# PERIPHERALS.net
KiCad netlist of a schematic drawn in Altium Designer
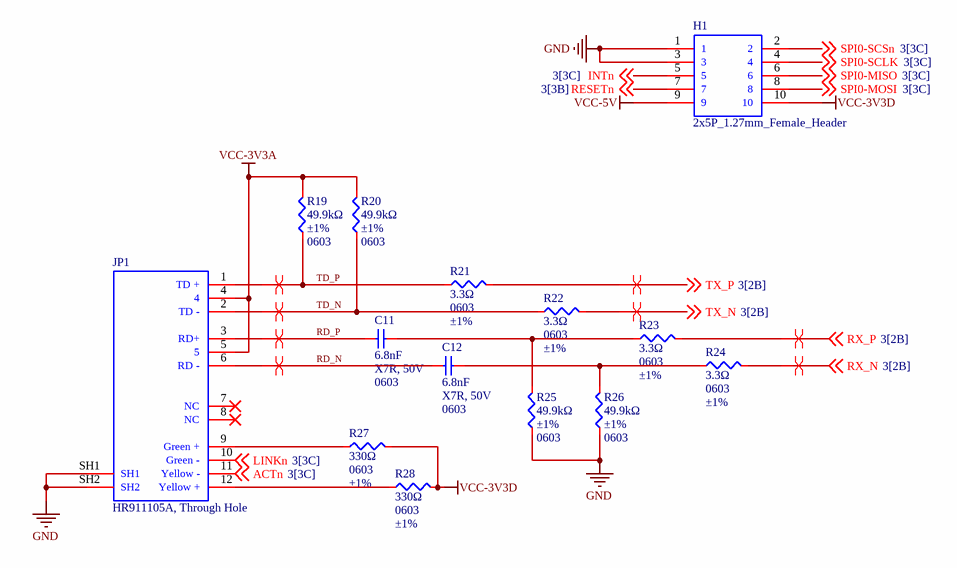
[diagram p0: PERIPHERALS.SchDoc]

(export (version "E")
  (design (tool "Eeschema 10.0.6"))
  (components
    (comp (ref "C11")
      (value "6.8nF")
      (footprint "C0603")
      (description "6.8nF ±10% 50V Ceramic Capacitor X7R 0603")
      (fields
        (field (name "MANUFACTURER") "YAGEO")
        (field (name "MFR. PART") "CC0603KRX7R9BB682")
        (field (name "TEMPERATURE COEFFICIENT") "X7R, 50V")
        (field (name "PACKAGE") "0603")
      )
      (libsource (lib "Capacitor") (part "C0603_MLCC_6.8nF_X7R_50V"))
    )
    (comp (ref "C12")
      (value "6.8nF")
      (footprint "C0603")
      (description "6.8nF ±10% 50V Ceramic Capacitor X7R 0603")
      (fields
        (field (name "MANUFACTURER") "YAGEO")
        (field (name "MFR. PART") "CC0603KRX7R9BB682")
        (field (name "TEMPERATURE COEFFICIENT") "X7R, 50V")
        (field (name "PACKAGE") "0603")
      )
      (libsource (lib "Capacitor") (part "C0603_MLCC_6.8nF_X7R_50V"))
    )
    (comp (ref "H1")
      (value "2x5P_1.27mm_Female_Header")
      (footprint "2x5P, 1.27mm, Female Header")
      (description "Female Header 10 Position 1.27mm Pitch Dual Row Through Hole -40℃~+105℃")
      (fields (field (name "MANUFACTURER") "Megastar") (field (name "MFR. PART") "ZX-PM1.27-2-5PU"))
      (libsource (lib "HEADER") (part "2x5P_1.27mm_Female_Header"))
    )
    (comp (ref "JP1")
      (value "HR911105A, Through Hole")
      (footprint "HR911105A")
      (description "CONN MOD JACK RJ45 TH")
      (fields
        (field (name "MANUFACTURER") "HANRUN(Zhongshan HanRun Elec)")
        (field (name "MFR. PART") "HR911105A")
      )
      (libsource (lib "CONNECTER") (part "HR911105A"))
    )
    (comp (ref "R19")
      (value "49.9kΩ")
      (footprint "R0603")
      (description "100mW Thick Film Resistor 75V ±100ppm/℃ ±1% 49.9kΩ 0603 Chip Resistor - Surface Mount ROHS")
      (fields
        (field (name "MANUFACTURER") "YAGEO")
        (field (name "MFR. PART") "RC0603FR-0749K9L")
        (field (name "TOLERANCE") "±1%")
        (field (name "PACKAGE") "0603")
      )
      (libsource (lib "Resistor") (part "R0603_49.9KΩ_±1%"))
    )
    (comp (ref "R20")
      (value "49.9kΩ")
      (footprint "R0603")
      (description "100mW Thick Film Resistor 75V ±100ppm/℃ ±1% 49.9kΩ 0603 Chip Resistor - Surface Mount ROHS")
      (fields
        (field (name "MANUFACTURER") "YAGEO")
        (field (name "MFR. PART") "RC0603FR-0749K9L")
        (field (name "TOLERANCE") "±1%")
        (field (name "PACKAGE") "0603")
      )
      (libsource (lib "Resistor") (part "R0603_49.9KΩ_±1%"))
    )
    (comp (ref "R21")
      (value "3.3Ω")
      (footprint "R0603")
      (description "3.3Ω ±1% 100mW 0603 Thick Film Resistor")
      (fields
        (field (name "MANUFACTURER") "UNI-ROYAL")
        (field (name "MFR. PART") "0603WAF330KT5E")
        (field (name "PACKAGE") "0603")
        (field (name "TOLERANCE") "±1%")
      )
      (libsource (lib "Resistor") (part "R0603_3.3Ω_±1%"))
    )
    (comp (ref "R22")
      (value "3.3Ω")
      (footprint "R0603")
      (description "3.3Ω ±1% 100mW 0603 Thick Film Resistor")
      (fields
        (field (name "MANUFACTURER") "UNI-ROYAL")
        (field (name "MFR. PART") "0603WAF330KT5E")
        (field (name "PACKAGE") "0603")
        (field (name "TOLERANCE") "±1%")
      )
      (libsource (lib "Resistor") (part "R0603_3.3Ω_±1%"))
    )
    (comp (ref "R23")
      (value "3.3Ω")
      (footprint "R0603")
      (description "3.3Ω ±1% 100mW 0603 Thick Film Resistor")
      (fields
        (field (name "MANUFACTURER") "UNI-ROYAL")
        (field (name "MFR. PART") "0603WAF330KT5E")
        (field (name "PACKAGE") "0603")
        (field (name "TOLERANCE") "±1%")
      )
      (libsource (lib "Resistor") (part "R0603_3.3Ω_±1%"))
    )
    (comp (ref "R24")
      (value "3.3Ω")
      (footprint "R0603")
      (description "3.3Ω ±1% 100mW 0603 Thick Film Resistor")
      (fields
        (field (name "MANUFACTURER") "UNI-ROYAL")
        (field (name "MFR. PART") "0603WAF330KT5E")
        (field (name "PACKAGE") "0603")
        (field (name "TOLERANCE") "±1%")
      )
      (libsource (lib "Resistor") (part "R0603_3.3Ω_±1%"))
    )
    (comp (ref "R25")
      (value "49.9kΩ")
      (footprint "R0603")
      (description "100mW Thick Film Resistor 75V ±100ppm/℃ ±1% 49.9kΩ 0603 Chip Resistor - Surface Mount ROHS")
      (fields
        (field (name "MANUFACTURER") "YAGEO")
        (field (name "MFR. PART") "RC0603FR-0749K9L")
        (field (name "TOLERANCE") "±1%")
        (field (name "PACKAGE") "0603")
      )
      (libsource (lib "Resistor") (part "R0603_49.9KΩ_±1%"))
    )
    (comp (ref "R26")
      (value "49.9kΩ")
      (footprint "R0603")
      (description "100mW Thick Film Resistor 75V ±100ppm/℃ ±1% 49.9kΩ 0603 Chip Resistor - Surface Mount ROHS")
      (fields
        (field (name "MANUFACTURER") "YAGEO")
        (field (name "MFR. PART") "RC0603FR-0749K9L")
        (field (name "TOLERANCE") "±1%")
        (field (name "PACKAGE") "0603")
      )
      (libsource (lib "Resistor") (part "R0603_49.9KΩ_±1%"))
    )
    (comp (ref "R27")
      (value "330Ω")
      (footprint "R0603")
      (description "100mW Thick Film Resistor 75V ±100ppm/℃ ±1% 330Ω 0603 Chip Resistor - Surface Mount ROHS")
      (fields
        (field (name "MANUFACTURER") "YAGEO")
        (field (name "MFR. PART") "RC0603FR-07330RL")
        (field (name "PACKAGE") "0603")
        (field (name "TOLERANCE") "±1%")
      )
      (libsource (lib "Resistor") (part "R0603_330Ω_±1%"))
    )
    (comp (ref "R28")
      (value "330Ω")
      (footprint "R0603")
      (description "100mW Thick Film Resistor 75V ±100ppm/℃ ±1% 330Ω 0603 Chip Resistor - Surface Mount ROHS")
      (fields
        (field (name "MANUFACTURER") "YAGEO")
        (field (name "MFR. PART") "RC0603FR-07330RL")
        (field (name "PACKAGE") "0603")
        (field (name "TOLERANCE") "±1%")
      )
      (libsource (lib "Resistor") (part "R0603_330Ω_±1%"))
    )
  )
  (nets
    (net (code "1") (name "/RD_N") (class "Default")
      (node (ref "C12") (pin "1") (pinfunction "1_1") (pintype "passive"))
      (node (ref "JP1") (pin "6") (pinfunction "RD_-_6") (pintype "passive"))
    )
    (net (code "2") (name "/RD_P") (class "Default")
      (node (ref "C11") (pin "1") (pinfunction "1_1") (pintype "passive"))
      (node (ref "JP1") (pin "3") (pinfunction "RD+_3") (pintype "passive"))
    )
    (net (code "3") (name "/TD_N") (class "Default")
      (node (ref "JP1") (pin "2") (pinfunction "TD_-_2") (pintype "passive"))
      (node (ref "R20") (pin "1") (pinfunction "1_1") (pintype "passive"))
      (node (ref "R22") (pin "1") (pinfunction "1_1") (pintype "passive"))
    )
    (net (code "4") (name "/TD_P") (class "Default")
      (node (ref "JP1") (pin "1") (pinfunction "TD_+_1") (pintype "passive"))
      (node (ref "R19") (pin "1") (pinfunction "1_1") (pintype "passive"))
      (node (ref "R21") (pin "1") (pinfunction "1_1") (pintype "passive"))
    )
    (net (code "5") (name "ACTn") (class "Default")
      (node (ref "JP1") (pin "11") (pinfunction "Yellow_-_11") (pintype "passive"))
    )
    (net (code "6") (name "GND") (class "Default")
      (node (ref "H1") (pin "1") (pinfunction "1_1") (pintype "passive"))
      (node (ref "H1") (pin "3") (pinfunction "3_3") (pintype "passive"))
      (node (ref "JP1") (pin "SH1") (pinfunction "SH1_SH1") (pintype "passive"))
      (node (ref "JP1") (pin "SH2") (pinfunction "SH2_SH2") (pintype "passive"))
      (node (ref "R25") (pin "1") (pinfunction "1_1") (pintype "passive"))
      (node (ref "R26") (pin "1") (pinfunction "1_1") (pintype "passive"))
    )
    (net (code "7") (name "INTn") (class "Default")
      (node (ref "H1") (pin "5") (pinfunction "5_5") (pintype "passive"))
    )
    (net (code "8") (name "LINKn") (class "Default")
      (node (ref "JP1") (pin "10") (pinfunction "Green_-_10") (pintype "passive"))
    )
    (net (code "9") (name "Net-(C11-Pad2)") (class "Default")
      (node (ref "C11") (pin "2") (pinfunction "2_2") (pintype "passive"))
      (node (ref "R23") (pin "1") (pinfunction "1_1") (pintype "passive"))
      (node (ref "R25") (pin "2") (pinfunction "2_2") (pintype "passive"))
    )
    (net (code "10") (name "Net-(C12-Pad2)") (class "Default")
      (node (ref "C12") (pin "2") (pinfunction "2_2") (pintype "passive"))
      (node (ref "R24") (pin "1") (pinfunction "1_1") (pintype "passive"))
      (node (ref "R26") (pin "2") (pinfunction "2_2") (pintype "passive"))
    )
    (net (code "11") (name "Net-(JP1-Green_+)") (class "Default")
      (node (ref "JP1") (pin "9") (pinfunction "Green_+_9") (pintype "passive"))
      (node (ref "R27") (pin "1") (pinfunction "1_1") (pintype "passive"))
    )
    (net (code "12") (name "Net-(JP1-Yellow_+)") (class "Default")
      (node (ref "JP1") (pin "12") (pinfunction "Yellow_+_12") (pintype "passive"))
      (node (ref "R28") (pin "1") (pinfunction "1_1") (pintype "passive"))
    )
    (net (code "13") (name "RESETn") (class "Default")
      (node (ref "H1") (pin "7") (pinfunction "7_7") (pintype "passive"))
    )
    (net (code "14") (name "RX_N") (class "Default")
      (node (ref "R24") (pin "2") (pinfunction "2_2") (pintype "passive"))
    )
    (net (code "15") (name "RX_P") (class "Default")
      (node (ref "R23") (pin "2") (pinfunction "2_2") (pintype "passive"))
    )
    (net (code "16") (name "SPI0-MISO") (class "Default")
      (node (ref "H1") (pin "6") (pinfunction "6_6") (pintype "passive"))
    )
    (net (code "17") (name "SPI0-MOSI") (class "Default")
      (node (ref "H1") (pin "8") (pinfunction "8_8") (pintype "passive"))
    )
    (net (code "18") (name "SPI0-SCLK") (class "Default")
      (node (ref "H1") (pin "4") (pinfunction "4_4") (pintype "passive"))
    )
    (net (code "19") (name "SPI0-SCSn") (class "Default")
      (node (ref "H1") (pin "2") (pinfunction "2_2") (pintype "passive"))
    )
    (net (code "20") (name "TX_N") (class "Default")
      (node (ref "R22") (pin "2") (pinfunction "2_2") (pintype "passive"))
    )
    (net (code "21") (name "TX_P") (class "Default")
      (node (ref "R21") (pin "2") (pinfunction "2_2") (pintype "passive"))
    )
    (net (code "22") (name "VCC-3V3A") (class "Default")
      (node (ref "JP1") (pin "4") (pinfunction "4_4") (pintype "passive"))
      (node (ref "JP1") (pin "5") (pinfunction "5_5") (pintype "passive"))
      (node (ref "R19") (pin "2") (pinfunction "2_2") (pintype "passive"))
      (node (ref "R20") (pin "2") (pinfunction "2_2") (pintype "passive"))
    )
    (net (code "23") (name "VCC-3V3D") (class "Default")
      (node (ref "H1") (pin "10") (pinfunction "10_10") (pintype "passive"))
      (node (ref "R27") (pin "2") (pinfunction "2_2") (pintype "passive"))
      (node (ref "R28") (pin "2") (pinfunction "2_2") (pintype "passive"))
    )
    (net (code "24") (name "VCC-5V") (class "Default")
      (node (ref "H1") (pin "9") (pinfunction "9_9") (pintype "passive"))
    )
    (net (code "25") (name "unconnected-(JP1-NC-Pad7)") (class "Default")
      (node (ref "JP1") (pin "7") (pinfunction "NC_7") (pintype "passive+no_connect"))
    )
    (net (code "26") (name "unconnected-(JP1-NC-Pad8)") (class "Default")
      (node (ref "JP1") (pin "8") (pinfunction "NC_8") (pintype "passive+no_connect"))
    )
  )
)
